# Circuit_Diagram.net
KiCad netlist of a schematic drawn in EAGLE
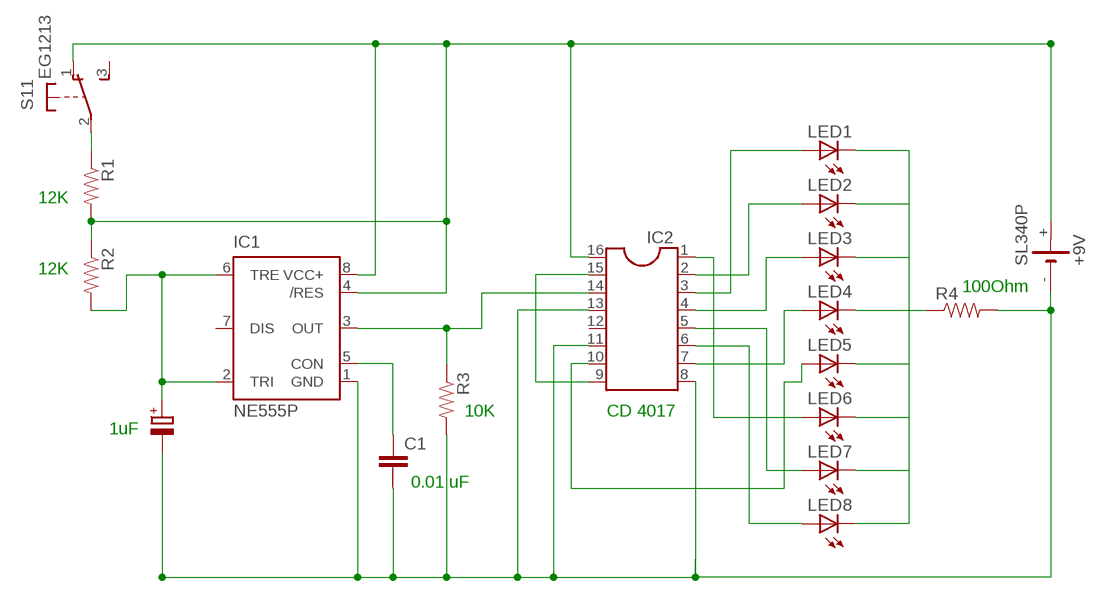
[diagram p0: schematic, sheet 1]

(export (version "E")
  (design (tool "Eeschema 10.0.6"))
  (components
    (comp (ref "+9V")
      (value "SL340P")
      (footprint "eagle-import:SL-340_P3.6V")
      (libsource (lib "eagle-import") (part "SL340P"))
    )
    (comp (ref "C1")
      (value "C2.5/6")
      (footprint "eagle-import:C2.5-6")
      (libsource (lib "eagle-import") (part "C2.5/6"))
    )
    (comp (ref "IC1")
      (value "NE555P")
      (footprint "eagle-import:DIL-08")
      (fields (field (name "MF") "Arrow Electronics") (field (name "MPN") "NE555N"))
      (libsource (lib "eagle-import") (part "NE555P"))
    )
    (comp (ref "IC2")
      (value "DIL16")
      (footprint "eagle-import:DIL16")
      (libsource (lib "eagle-import") (part "DIL16"))
    )
    (comp (ref "LED1")
      (value "LEDB156")
      (footprint "eagle-import:Q62902-B156")
      (libsource (lib "eagle-import") (part "LEDB156"))
    )
    (comp (ref "LED2")
      (value "LEDB156")
      (footprint "eagle-import:Q62902-B156")
      (libsource (lib "eagle-import") (part "LEDB156"))
    )
    (comp (ref "LED3")
      (value "LEDB156")
      (footprint "eagle-import:Q62902-B156")
      (libsource (lib "eagle-import") (part "LEDB156"))
    )
    (comp (ref "LED4")
      (value "LEDB156")
      (footprint "eagle-import:Q62902-B156")
      (libsource (lib "eagle-import") (part "LEDB156"))
    )
    (comp (ref "LED5")
      (value "LEDB156")
      (footprint "eagle-import:Q62902-B156")
      (libsource (lib "eagle-import") (part "LEDB156"))
    )
    (comp (ref "LED6")
      (value "LEDB156")
      (footprint "eagle-import:Q62902-B156")
      (libsource (lib "eagle-import") (part "LEDB156"))
    )
    (comp (ref "LED7")
      (value "LEDB156")
      (footprint "eagle-import:Q62902-B156")
      (libsource (lib "eagle-import") (part "LEDB156"))
    )
    (comp (ref "LED8")
      (value "LEDB156")
      (footprint "eagle-import:Q62902-B156")
      (libsource (lib "eagle-import") (part "LEDB156"))
    )
    (comp (ref "R1")
      (value "RESISTORAXIAL-0.3")
      (footprint "eagle-import:AXIAL-0.3")
      (libsource (lib "eagle-import") (part "RESISTORAXIAL-0.3"))
    )
    (comp (ref "R2")
      (value "RESISTORAXIAL-0.3")
      (footprint "eagle-import:AXIAL-0.3")
      (libsource (lib "eagle-import") (part "RESISTORAXIAL-0.3"))
    )
    (comp (ref "R3")
      (value "RESISTORAXIAL-0.3")
      (footprint "eagle-import:AXIAL-0.3")
      (libsource (lib "eagle-import") (part "RESISTORAXIAL-0.3"))
    )
    (comp (ref "R4")
      (value "RESISTORAXIAL-0.3")
      (footprint "eagle-import:AXIAL-0.3")
      (libsource (lib "eagle-import") (part "RESISTORAXIAL-0.3"))
    )
    (comp (ref "S1")
      (value "EG1213")
      (footprint "eagle-import:EG1213")
      (libsource (lib "eagle-import") (part "EG1213"))
    )
  )
  (nets
    (net (code "1") (name "Net-(IC1-CON)") (class "Default")
      (node (ref "C1") (pin "1") (pinfunction "1_1") (pintype "passive"))
      (node (ref "IC1") (pin "5") (pinfunction "CON_5") (pintype "input"))
    )
    (net (code "2") (name "Net-(IC1-GND)") (class "Default")
      (node (ref "+9V") (pin "-") (pinfunction "-_-") (pintype "passive"))
      (node (ref "C1") (pin "2") (pinfunction "2_2") (pintype "passive"))
      (node (ref "IC1") (pin "1") (pinfunction "GND_1") (pintype "power_in"))
      (node (ref "IC2") (pin "11") (pinfunction "11_11") (pintype "passive"))
      (node (ref "IC2") (pin "13") (pinfunction "13_13") (pintype "passive"))
      (node (ref "IC2") (pin "8") (pinfunction "8_8") (pintype "passive"))
      (node (ref "R3") (pin "P$2") (pinfunction "2_P$2") (pintype "passive"))
      (node (ref "R4") (pin "P$2") (pinfunction "2_P$2") (pintype "passive"))
    )
    (net (code "3") (name "Net-(IC1-OUT)") (class "Default")
      (node (ref "IC1") (pin "3") (pinfunction "OUT_3") (pintype "output"))
      (node (ref "IC2") (pin "14") (pinfunction "14_14") (pintype "passive"))
      (node (ref "R3") (pin "P$1") (pinfunction "1_P$1") (pintype "passive"))
    )
    (net (code "4") (name "Net-(IC1-TRE)") (class "Default")
      (node (ref "IC1") (pin "2") (pinfunction "TRI_2") (pintype "input"))
      (node (ref "IC1") (pin "6") (pinfunction "TRE_6") (pintype "input"))
      (node (ref "R2") (pin "P$2") (pinfunction "2_P$2") (pintype "passive"))
    )
    (net (code "5") (name "Net-(IC1-VCC+)") (class "Default")
      (node (ref "+9V") (pin "+") (pinfunction "+_+") (pintype "passive"))
      (node (ref "IC1") (pin "4") (pinfunction "/RES_4") (pintype "input"))
      (node (ref "IC1") (pin "8") (pinfunction "VCC+_8") (pintype "power_in"))
      (node (ref "IC2") (pin "16") (pinfunction "16_16") (pintype "passive"))
      (node (ref "R1") (pin "P$2") (pinfunction "2_P$2") (pintype "passive"))
      (node (ref "R2") (pin "P$1") (pinfunction "1_P$1") (pintype "passive"))
      (node (ref "S1") (pin "1") (pinfunction "O_1") (pintype "passive"))
    )
    (net (code "6") (name "Net-(IC2-Pad1)") (class "Default")
      (node (ref "IC2") (pin "1") (pinfunction "1_1") (pintype "passive"))
      (node (ref "LED6") (pin "A") (pinfunction "A_A") (pintype "passive"))
    )
    (net (code "7") (name "Net-(IC2-Pad2)") (class "Default")
      (node (ref "IC2") (pin "2") (pinfunction "2_2") (pintype "passive"))
      (node (ref "LED2") (pin "A") (pinfunction "A_A") (pintype "passive"))
    )
    (net (code "8") (name "Net-(IC2-Pad3)") (class "Default")
      (node (ref "IC2") (pin "3") (pinfunction "3_3") (pintype "passive"))
      (node (ref "LED1") (pin "A") (pinfunction "A_A") (pintype "passive"))
    )
    (net (code "9") (name "Net-(IC2-Pad4)") (class "Default")
      (node (ref "IC2") (pin "4") (pinfunction "4_4") (pintype "passive"))
      (node (ref "LED3") (pin "A") (pinfunction "A_A") (pintype "passive"))
    )
    (net (code "10") (name "Net-(IC2-Pad5)") (class "Default")
      (node (ref "IC2") (pin "5") (pinfunction "5_5") (pintype "passive"))
      (node (ref "LED7") (pin "A") (pinfunction "A_A") (pintype "passive"))
    )
    (net (code "11") (name "Net-(IC2-Pad6)") (class "Default")
      (node (ref "IC2") (pin "6") (pinfunction "6_6") (pintype "passive"))
      (node (ref "LED8") (pin "A") (pinfunction "A_A") (pintype "passive"))
    )
    (net (code "12") (name "Net-(IC2-Pad7)") (class "Default")
      (node (ref "IC2") (pin "7") (pinfunction "7_7") (pintype "passive"))
      (node (ref "LED4") (pin "A") (pinfunction "A_A") (pintype "passive"))
    )
    (net (code "13") (name "Net-(IC2-Pad10)") (class "Default")
      (node (ref "IC2") (pin "10") (pinfunction "10_10") (pintype "passive"))
      (node (ref "LED5") (pin "A") (pinfunction "A_A") (pintype "passive"))
    )
    (net (code "14") (name "Net-(IC2-Pad15)") (class "Default")
      (node (ref "IC2") (pin "15") (pinfunction "15_15") (pintype "passive"))
      (node (ref "IC2") (pin "9") (pinfunction "9_9") (pintype "passive"))
    )
    (net (code "15") (name "Net-(LED1-C)") (class "Default")
      (node (ref "LED1") (pin "K") (pinfunction "C_K") (pintype "passive"))
      (node (ref "LED2") (pin "K") (pinfunction "C_K") (pintype "passive"))
      (node (ref "LED3") (pin "K") (pinfunction "C_K") (pintype "passive"))
      (node (ref "LED4") (pin "K") (pinfunction "C_K") (pintype "passive"))
      (node (ref "LED5") (pin "K") (pinfunction "C_K") (pintype "passive"))
      (node (ref "LED6") (pin "K") (pinfunction "C_K") (pintype "passive"))
      (node (ref "LED7") (pin "K") (pinfunction "C_K") (pintype "passive"))
      (node (ref "LED8") (pin "K") (pinfunction "C_K") (pintype "passive"))
      (node (ref "R4") (pin "P$1") (pinfunction "1_P$1") (pintype "passive"))
    )
    (net (code "16") (name "Net-(R1-1)") (class "Default")
      (node (ref "R1") (pin "P$1") (pinfunction "1_P$1") (pintype "passive"))
      (node (ref "S1") (pin "2") (pinfunction "P_2") (pintype "passive"))
    )
    (net (code "17") (name "unconnected-(IC1-DIS-Pad7)") (class "Default")
      (node (ref "IC1") (pin "7") (pinfunction "DIS_7") (pintype "input"))
    )
    (net (code "18") (name "unconnected-(IC2-Pad12)") (class "Default")
      (node (ref "IC2") (pin "12") (pinfunction "12_12") (pintype "passive"))
    )
    (net (code "19") (name "unconnected-(S1A-S-Pad3)") (class "Default")
      (node (ref "S1") (pin "3") (pinfunction "S_3") (pintype "passive"))
    )
  )
)
